# SCH_DVR8825V5_2024-05-12.net
KiCad netlist of a schematic drawn in EasyEDA
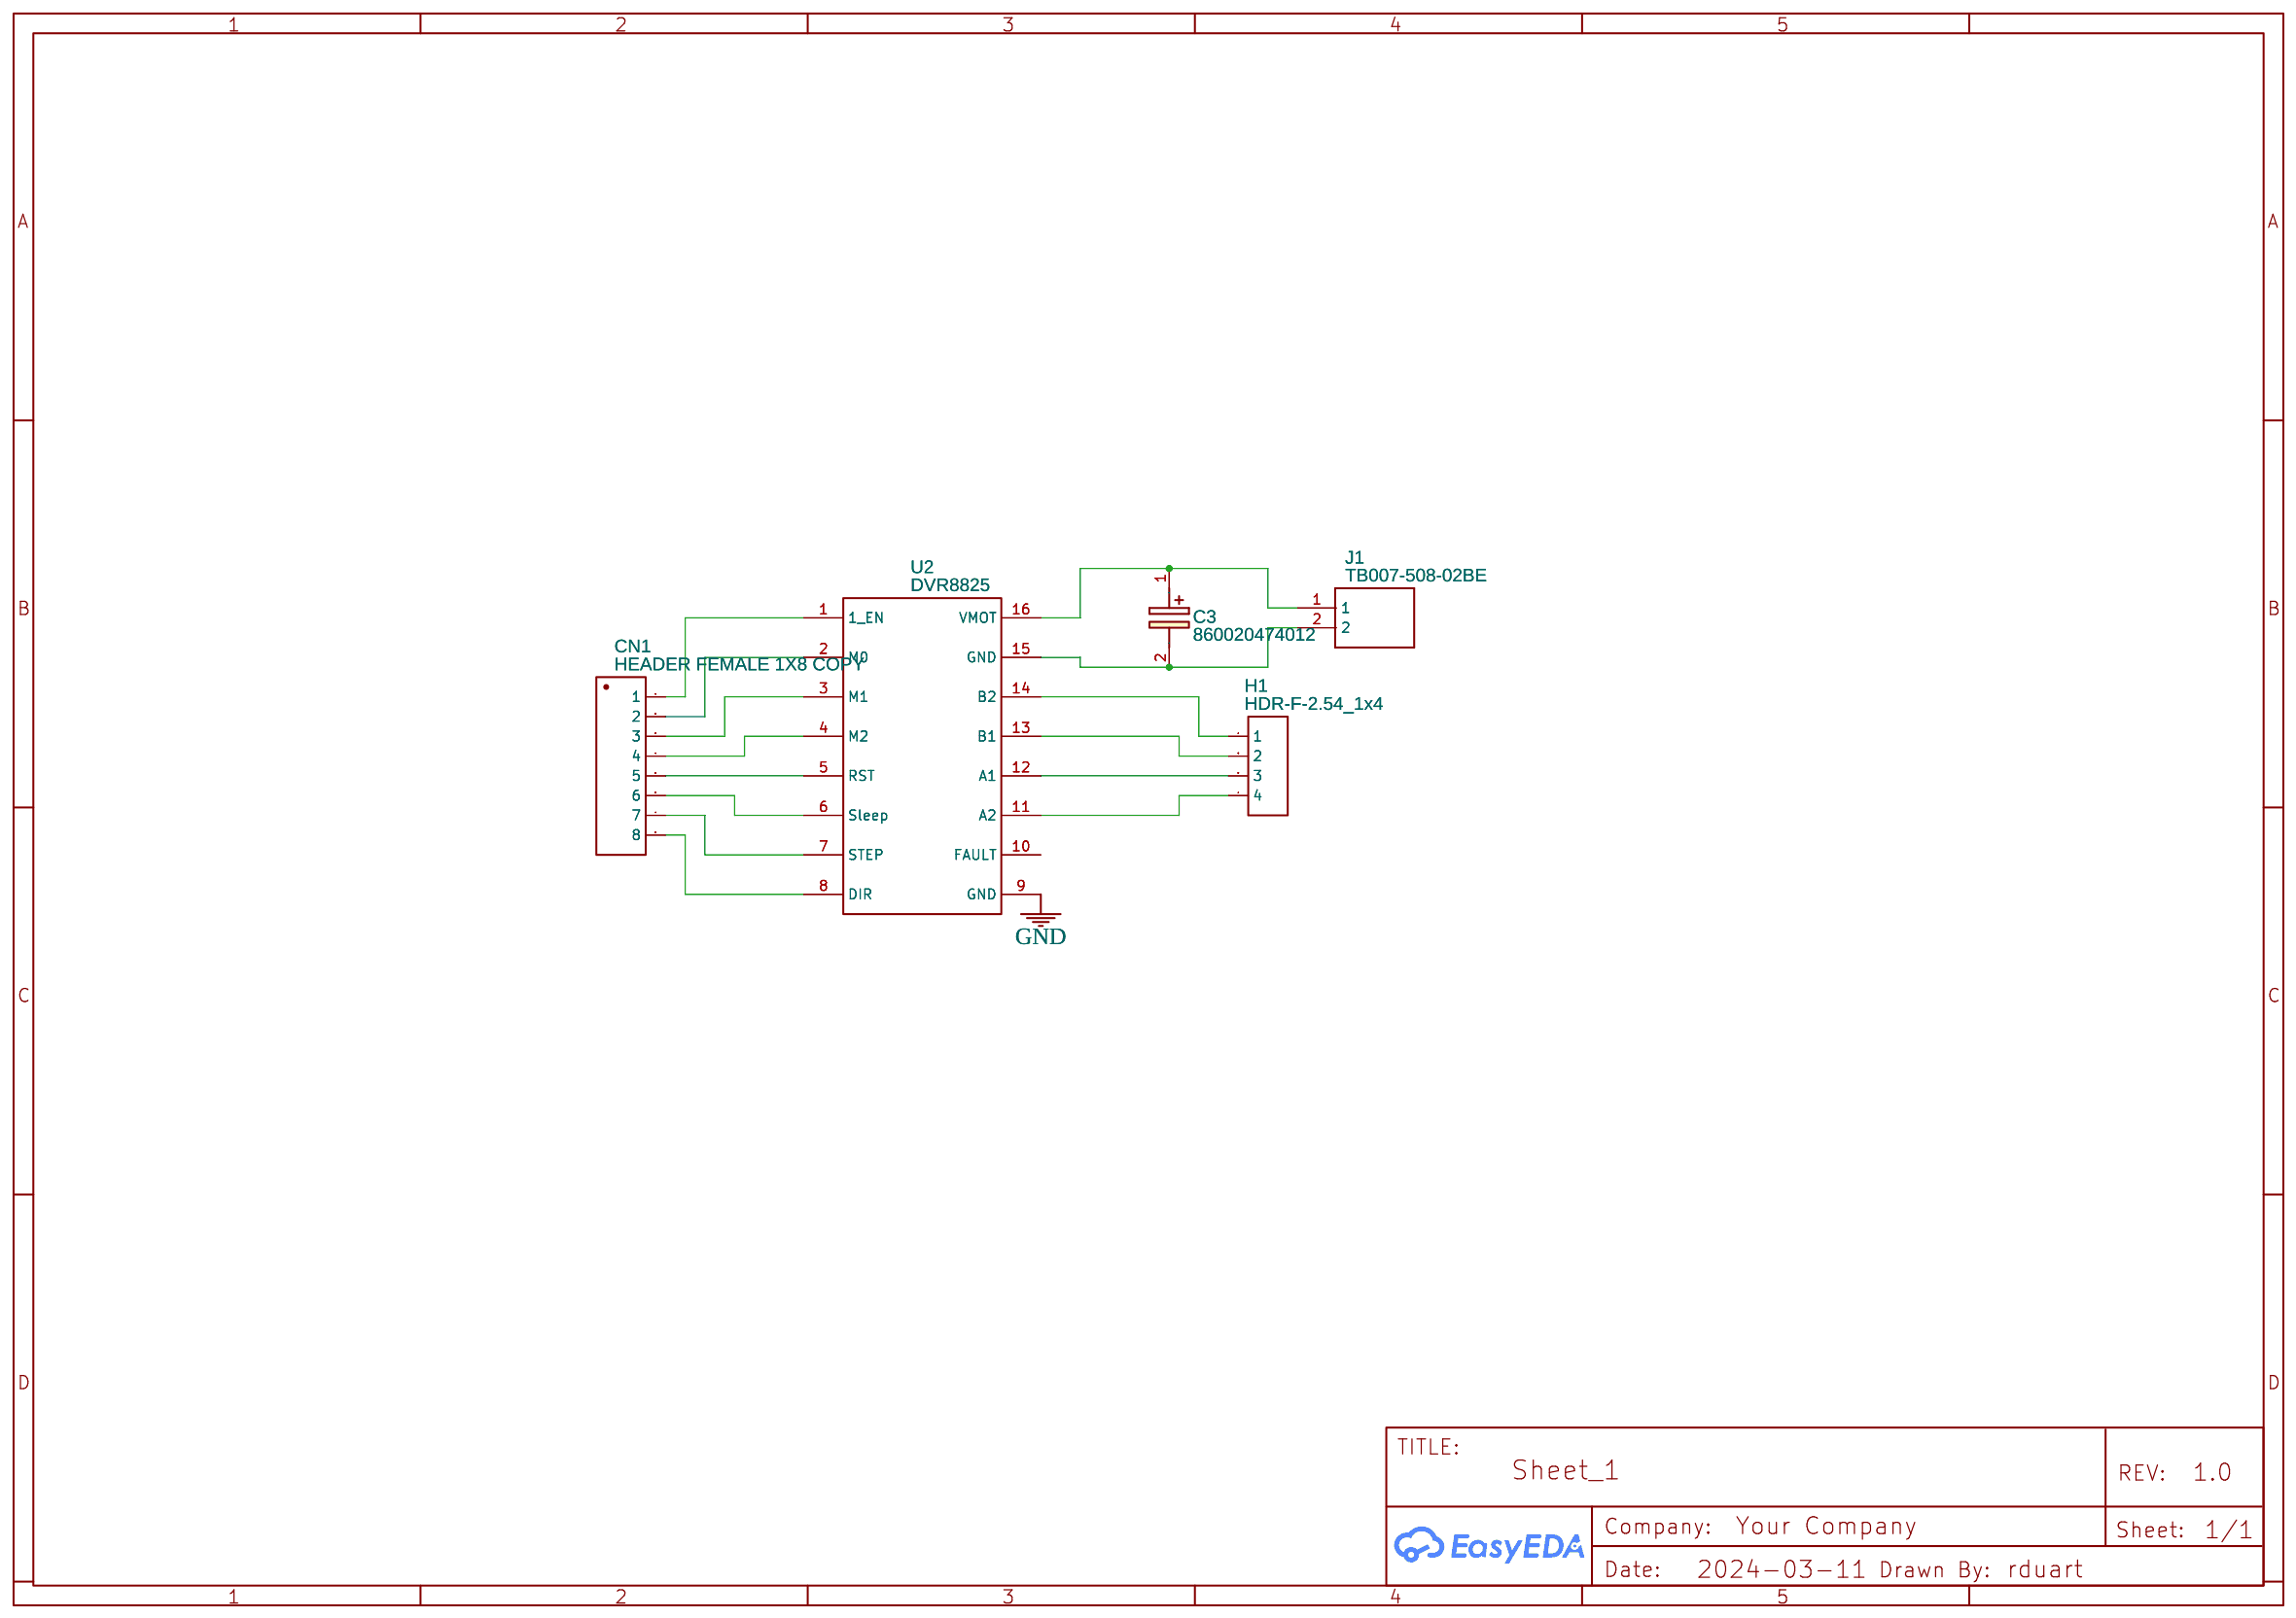
[diagram p0: schematic sheet]

(export (version "E")
  (design (tool "Eeschema 10.0.6"))
  (components
    (comp (ref "C3") (value "860020474012") (libsource (lib "") (part "860020474012")))
    (comp (ref "CN1") (value "HEADER FEMALE 1X8 COPY") (libsource (lib "") (part "HEADER FEMALE 1X8 COPY")))
    (comp (ref "H1") (value "HDR-F-2.54_1x4") (libsource (lib "") (part "HDR-F-2.54_1x4")))
    (comp (ref "J1") (value "TB007-508-02BE") (libsource (lib "") (part "TB007-508-02BE")))
    (comp (ref "U2")
      (value "DVR8825")
      (fields (field (name "Manufacturer Part") "https://www.pololu.com/product/2133"))
      (libsource (lib "") (part "DVR8825"))
    )
  )
  (nets
    (net (code "1") (name "GND") (class "Default")
      (node (ref "U2") (pin "9") (pinfunction "GND_9") (pintype "unspecified"))
    )
    (net (code "2") (name "Net-(C3-+)") (class "Default")
      (node (ref "C3") (pin "1") (pinfunction "+_1") (pintype "bidirectional"))
      (node (ref "J1") (pin "1") (pinfunction "1_1") (pintype "bidirectional"))
      (node (ref "U2") (pin "16") (pinfunction "VMOT_16") (pintype "unspecified"))
    )
    (net (code "3") (name "Net-(C3--)") (class "Default")
      (node (ref "C3") (pin "2") (pinfunction "-_2") (pintype "bidirectional"))
      (node (ref "J1") (pin "2") (pinfunction "2_2") (pintype "bidirectional"))
      (node (ref "U2") (pin "15") (pinfunction "GND_15") (pintype "unspecified"))
    )
    (net (code "4") (name "Net-(U2-1_EN)") (class "Default")
      (node (ref "CN1") (pin "1") (pinfunction "1_1") (pintype "unspecified"))
      (node (ref "U2") (pin "1") (pinfunction "1_EN_1") (pintype "unspecified"))
    )
    (net (code "5") (name "Net-(U2-A1)") (class "Default")
      (node (ref "H1") (pin "3") (pinfunction "3_3") (pintype "unspecified"))
      (node (ref "U2") (pin "12") (pinfunction "A1_12") (pintype "unspecified"))
    )
    (net (code "6") (name "Net-(U2-A2)") (class "Default")
      (node (ref "H1") (pin "4") (pinfunction "4_4") (pintype "unspecified"))
      (node (ref "U2") (pin "11") (pinfunction "A2_11") (pintype "unspecified"))
    )
    (net (code "7") (name "Net-(U2-B1)") (class "Default")
      (node (ref "H1") (pin "2") (pinfunction "2_2") (pintype "unspecified"))
      (node (ref "U2") (pin "13") (pinfunction "B1_13") (pintype "unspecified"))
    )
    (net (code "8") (name "Net-(U2-B2)") (class "Default")
      (node (ref "H1") (pin "1") (pinfunction "1_1") (pintype "unspecified"))
      (node (ref "U2") (pin "14") (pinfunction "B2_14") (pintype "unspecified"))
    )
    (net (code "9") (name "Net-(U2-DIR)") (class "Default")
      (node (ref "CN1") (pin "8") (pinfunction "8_8") (pintype "unspecified"))
      (node (ref "U2") (pin "8") (pinfunction "DIR_8") (pintype "unspecified"))
    )
    (net (code "10") (name "Net-(U2-M0)") (class "Default")
      (node (ref "CN1") (pin "2") (pinfunction "2_2") (pintype "unspecified"))
      (node (ref "U2") (pin "2") (pinfunction "M0_2") (pintype "unspecified"))
    )
    (net (code "11") (name "Net-(U2-M1)") (class "Default")
      (node (ref "CN1") (pin "3") (pinfunction "3_3") (pintype "unspecified"))
      (node (ref "U2") (pin "3") (pinfunction "M1_3") (pintype "unspecified"))
    )
    (net (code "12") (name "Net-(U2-M2)") (class "Default")
      (node (ref "CN1") (pin "4") (pinfunction "4_4") (pintype "unspecified"))
      (node (ref "U2") (pin "4") (pinfunction "M2_4") (pintype "unspecified"))
    )
    (net (code "13") (name "Net-(U2-RST)") (class "Default")
      (node (ref "CN1") (pin "5") (pinfunction "5_5") (pintype "unspecified"))
      (node (ref "U2") (pin "5") (pinfunction "RST_5") (pintype "unspecified"))
    )
    (net (code "14") (name "Net-(U2-STEP)") (class "Default")
      (node (ref "CN1") (pin "7") (pinfunction "7_7") (pintype "unspecified"))
      (node (ref "U2") (pin "7") (pinfunction "STEP_7") (pintype "unspecified"))
    )
    (net (code "15") (name "Net-(U2-Sleep)") (class "Default")
      (node (ref "CN1") (pin "6") (pinfunction "6_6") (pintype "unspecified"))
      (node (ref "U2") (pin "6") (pinfunction "Sleep_6") (pintype "unspecified"))
    )
    (net (code "16") (name "unconnected-(U2-FAULT-Pad10)") (class "Default")
      (node (ref "U2") (pin "10") (pinfunction "FAULT_10") (pintype "unspecified"))
    )
  )
)
